# Sheet1.net
KiCad netlist of a schematic drawn in Altium Designer
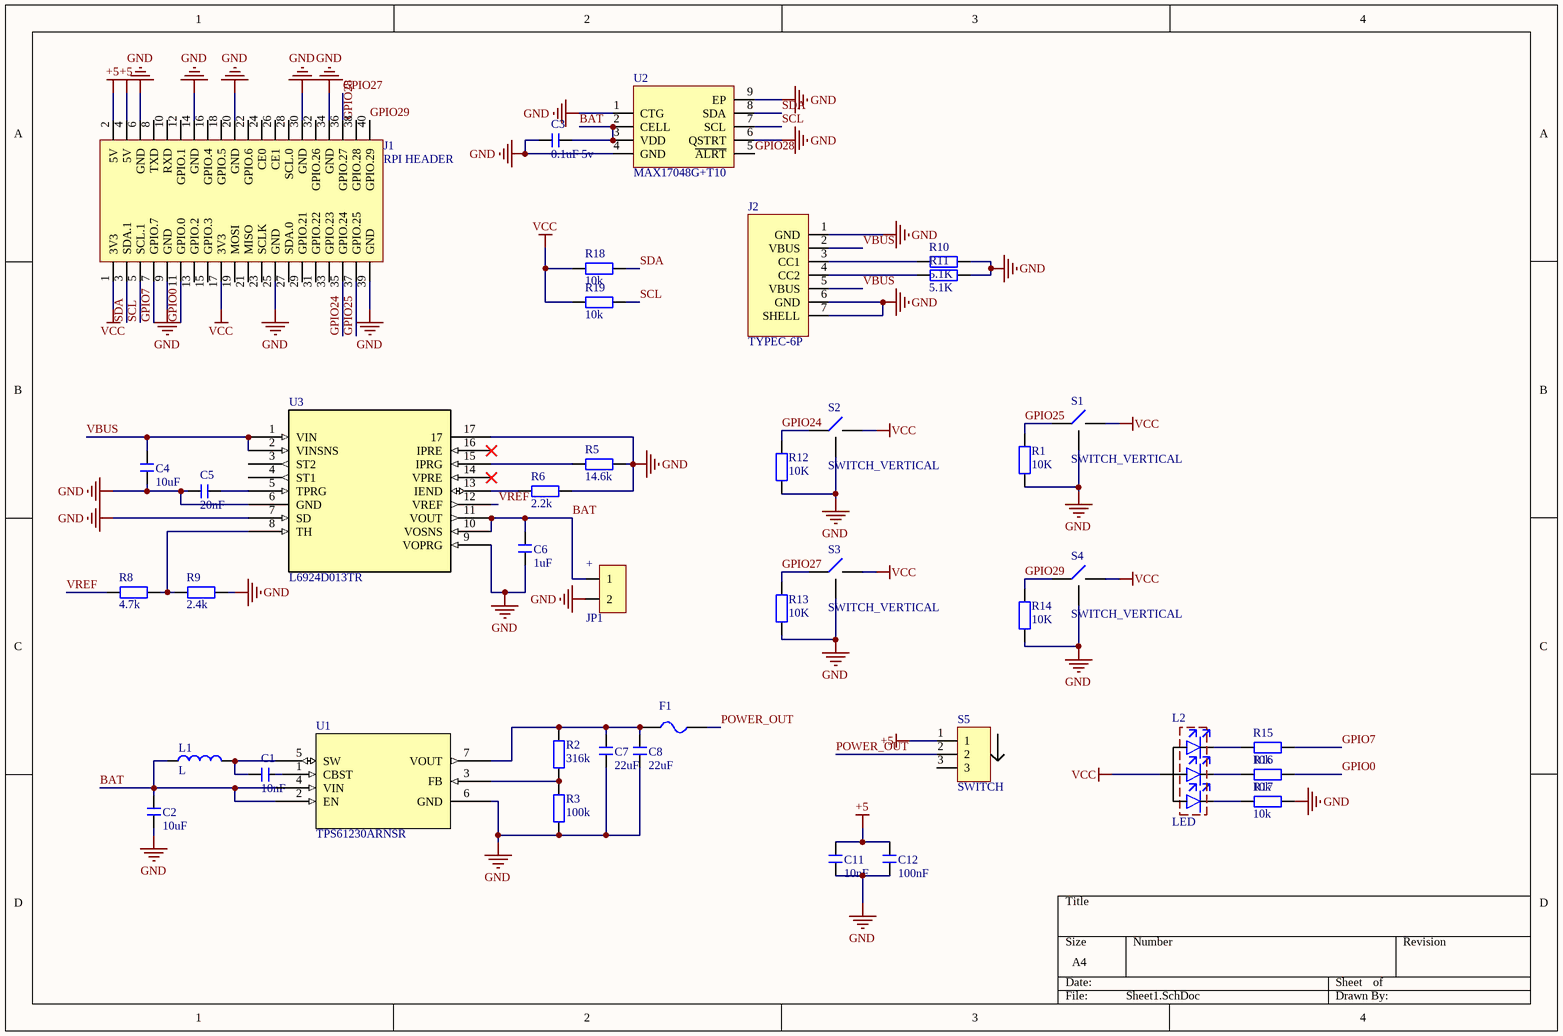
[diagram p0: Sheet1.SchDoc]

(export (version "E")
  (design (tool "Eeschema 10.0.6"))
  (components
    (comp (ref "C1")
      (value "10nF")
      (footprint "C 0603_M")
      (description "无极性贴片电容")
      (libsource (lib "元件库2") (part "C"))
    )
    (comp (ref "C2")
      (value "10uF")
      (footprint "C 0603_M")
      (description "无极性贴片电容")
      (libsource (lib "元件库2") (part "C"))
    )
    (comp (ref "C3")
      (value "0.1uF 5v")
      (footprint "C 0603_M")
      (description "无极性贴片电容")
      (libsource (lib "元件库2") (part "C"))
    )
    (comp (ref "C4")
      (value "10uF")
      (footprint "C 0603_M")
      (description "无极性贴片电容")
      (libsource (lib "元件库2") (part "C"))
    )
    (comp (ref "C5")
      (value "20nF")
      (footprint "C 0603_M")
      (description "无极性贴片电容")
      (libsource (lib "元件库2") (part "C"))
    )
    (comp (ref "C6")
      (value "1uF")
      (footprint "C 0603_M")
      (description "无极性贴片电容")
      (libsource (lib "元件库2") (part "C"))
    )
    (comp (ref "C7")
      (value "22uF")
      (footprint "C 0603_M")
      (description "无极性贴片电容")
      (libsource (lib "元件库2") (part "C"))
    )
    (comp (ref "C8")
      (value "22uF")
      (footprint "C 0603_M")
      (description "无极性贴片电容")
      (libsource (lib "元件库2") (part "C"))
    )
    (comp (ref "C11")
      (value "10nF")
      (footprint "C 0603_M")
      (description "无极性贴片电容")
      (libsource (lib "元件库2") (part "C"))
    )
    (comp (ref "C12")
      (value "100nF")
      (footprint "C 0603_M")
      (description "无极性贴片电容")
      (libsource (lib "元件库2") (part "C"))
    )
    (comp (ref "F1")
      (value "MSMD200-8V 2A")
      (footprint "FU 1206")
      (description "贴片保险丝")
      (fields (field (name "版权归属") "源创客"))
      (libsource (lib "Altium Designer 3D元件库") (part "FU"))
    )
    (comp (ref "J1")
      (value "RPI HEADER")
      (footprint "HEADER 2*20 BACK")
      (libsource (lib "Schlib1") (part "RPI HEADER"))
    )
    (comp (ref "J2")
      (value "TYPEC-6P")
      (footprint "TYPEC-6P-SMD")
      (libsource (lib "Schlib1") (part "TYPEC-6P"))
    )
    (comp (ref "JP1") (value "PH2.0 2P") (footprint "PH2.0 2P") (libsource (lib "Schlib1") (part "PH2.0 2P")))
    (comp (ref "L1") (value "L") (footprint "L SMD") (libsource (lib "Schlib1") (part "L")))
    (comp (ref "L2")
      (value "LED")
      (footprint "FM-3510RGBA-SG")
      (libsource (lib "Schlib1") (part "RGBLED_VERTICAL"))
    )
    (comp (ref "R1")
      (value "10K")
      (footprint "R 0603-HP")
      (description "贴片电阻")
      (fields (field (name "版权归属") "源创客"))
      (libsource (lib "Altium Designer 3D元件库") (part "R"))
    )
    (comp (ref "R2")
      (value "316k")
      (footprint "R 0603-HP")
      (description "贴片电阻")
      (fields (field (name "版权归属") "源创客"))
      (libsource (lib "Altium Designer 3D元件库") (part "R"))
    )
    (comp (ref "R3")
      (value "100k")
      (footprint "R 0603-HP")
      (description "贴片电阻")
      (fields (field (name "版权归属") "源创客"))
      (libsource (lib "Altium Designer 3D元件库") (part "R"))
    )
    (comp (ref "R5")
      (value "14.6k")
      (footprint "R 0603-HP")
      (description "贴片电阻")
      (fields (field (name "版权归属") "源创客"))
      (libsource (lib "Altium Designer 3D元件库") (part "R"))
    )
    (comp (ref "R6")
      (value "2.2k")
      (footprint "R 0603-HP")
      (description "贴片电阻")
      (fields (field (name "版权归属") "源创客"))
      (libsource (lib "Altium Designer 3D元件库") (part "R"))
    )
    (comp (ref "R8")
      (value "4.7k")
      (footprint "R 0603-HP")
      (description "贴片电阻")
      (fields (field (name "版权归属") "源创客"))
      (libsource (lib "Altium Designer 3D元件库") (part "R"))
    )
    (comp (ref "R9")
      (value "2.4k")
      (footprint "R 0603-HP")
      (description "贴片电阻")
      (fields (field (name "版权归属") "源创客"))
      (libsource (lib "Altium Designer 3D元件库") (part "R"))
    )
    (comp (ref "R10")
      (value "5.1K")
      (footprint "R 0603")
      (description "贴片电阻")
      (fields (field (name "版权归属") "源创客"))
      (libsource (lib "Altium Designer 3D元件库") (part "R"))
    )
    (comp (ref "R11")
      (value "5.1K")
      (footprint "R 0603")
      (description "贴片电阻")
      (fields (field (name "版权归属") "源创客"))
      (libsource (lib "Altium Designer 3D元件库") (part "R"))
    )
    (comp (ref "R12")
      (value "10K")
      (footprint "R 0603-HP")
      (description "贴片电阻")
      (fields (field (name "版权归属") "源创客"))
      (libsource (lib "Altium Designer 3D元件库") (part "R"))
    )
    (comp (ref "R13")
      (value "10K")
      (footprint "R 0603-HP")
      (description "贴片电阻")
      (fields (field (name "版权归属") "源创客"))
      (libsource (lib "Altium Designer 3D元件库") (part "R"))
    )
    (comp (ref "R14")
      (value "10K")
      (footprint "R 0603-HP")
      (description "贴片电阻")
      (fields (field (name "版权归属") "源创客"))
      (libsource (lib "Altium Designer 3D元件库") (part "R"))
    )
    (comp (ref "R15")
      (value "10k")
      (footprint "R 0603-HP")
      (description "贴片电阻")
      (fields (field (name "版权归属") "源创客"))
      (libsource (lib "Altium Designer 3D元件库") (part "R"))
    )
    (comp (ref "R16")
      (value "10k")
      (footprint "R 0603-HP")
      (description "贴片电阻")
      (fields (field (name "版权归属") "源创客"))
      (libsource (lib "Altium Designer 3D元件库") (part "R"))
    )
    (comp (ref "R17")
      (value "10k")
      (footprint "R 0603-HP")
      (description "贴片电阻")
      (fields (field (name "版权归属") "源创客"))
      (libsource (lib "Altium Designer 3D元件库") (part "R"))
    )
    (comp (ref "R18")
      (value "10k")
      (footprint "R 0603-HP")
      (description "贴片电阻")
      (fields (field (name "版权归属") "源创客"))
      (libsource (lib "Altium Designer 3D元件库") (part "R"))
    )
    (comp (ref "R19")
      (value "10k")
      (footprint "R 0603-HP")
      (description "贴片电阻")
      (fields (field (name "版权归属") "源创客"))
      (libsource (lib "Altium Designer 3D元件库") (part "R"))
    )
    (comp (ref "S1")
      (value "SWITCH_VERTICAL")
      (footprint "TA3-2W2-V-T/R")
      (libsource (lib "Schlib1") (part "SWITCH_VERTICAL"))
    )
    (comp (ref "S2")
      (value "SWITCH_VERTICAL")
      (footprint "TA3-2W2-V-T/R")
      (libsource (lib "Schlib1") (part "SWITCH_VERTICAL"))
    )
    (comp (ref "S3")
      (value "SWITCH_VERTICAL")
      (footprint "TA3-2W2-V-T/R")
      (libsource (lib "Schlib1") (part "SWITCH_VERTICAL"))
    )
    (comp (ref "S4")
      (value "SWITCH_VERTICAL")
      (footprint "TA3-2W2-V-T/R")
      (libsource (lib "Schlib1") (part "SWITCH_VERTICAL"))
    )
    (comp (ref "S5") (value "SWITCH") (footprint "SWITCH") (libsource (lib "Schlib1") (part "SWITCH")))
    (comp (ref "U1")
      (value "TPS61230ARNSR")
      (footprint "VQFN7_2X2_TEX-M")
      (description "No Description Available")
      (fields (field (name "COPYRIGHT") "Copyright (C) 2022 Ultra Librarian. All rights reserved."))
      (libsource (lib "Schlib1") (part "TPS61230ARNSR"))
    )
    (comp (ref "U2")
      (value "MAX17048G+T10")
      (footprint "TDFN-8_EP")
      (libsource (lib "Schlib1") (part "MAX17048G+T10"))
    )
    (comp (ref "U3")
      (value "L6924D013TR")
      (footprint "VFQFPN-16_STM-M")
      (description "No Description Available")
      (fields (field (name "COPYRIGHT") "Copyright (C) 2021 Accelerated Designs. All rights reserved"))
      (libsource (lib "Schlib1") (part "L6924D013TR"))
    )
  )
  (nets
    (net (code "1") (name "+5") (class "Default")
      (node (ref "C11") (pin "2") (pinfunction "2_2") (pintype "passive"))
      (node (ref "C12") (pin "2") (pinfunction "2_2") (pintype "passive"))
      (node (ref "J1") (pin "2") (pinfunction "5V_2") (pintype "passive"))
      (node (ref "J1") (pin "4") (pinfunction "5V_4") (pintype "passive"))
      (node (ref "S5") (pin "1") (pinfunction "1_1") (pintype "passive"))
    )
    (net (code "2") (name "/BAT") (class "Default")
      (node (ref "C2") (pin "1") (pinfunction "1_1") (pintype "passive"))
      (node (ref "C3") (pin "2") (pinfunction "2_2") (pintype "passive"))
      (node (ref "C6") (pin "2") (pinfunction "2_2") (pintype "passive"))
      (node (ref "JP1") (pin "1") (pinfunction "1_1") (pintype "passive"))
      (node (ref "L1") (pin "1") (pinfunction "1_1") (pintype "passive"))
      (node (ref "U1") (pin "2") (pinfunction "EN_2") (pintype "input"))
      (node (ref "U1") (pin "4") (pinfunction "VIN_4") (pintype "input"))
      (node (ref "U2") (pin "2") (pinfunction "CELL_2") (pintype "passive"))
      (node (ref "U2") (pin "3") (pinfunction "VDD_3") (pintype "passive"))
      (node (ref "U3") (pin "10") (pinfunction "VOSNS_10") (pintype "input"))
      (node (ref "U3") (pin "11") (pinfunction "VOUT_11") (pintype "output"))
    )
    (net (code "3") (name "/GPIO0") (class "Default")
      (node (ref "J1") (pin "11") (pinfunction "GPIO.0_11") (pintype "passive"))
      (node (ref "R16") (pin "1") (pinfunction "1_1") (pintype "passive"))
    )
    (net (code "4") (name "/GPIO7") (class "Default")
      (node (ref "J1") (pin "7") (pinfunction "GPIO.7_7") (pintype "passive"))
      (node (ref "R15") (pin "1") (pinfunction "1_1") (pintype "passive"))
    )
    (net (code "5") (name "/GPIO24") (class "Default")
      (node (ref "J1") (pin "35") (pinfunction "GPIO.24_35") (pintype "passive"))
      (node (ref "R12") (pin "1") (pinfunction "1_1") (pintype "passive"))
      (node (ref "S2") (pin "1") (pinfunction "1_1") (pintype "passive"))
    )
    (net (code "6") (name "/GPIO25") (class "Default")
      (node (ref "J1") (pin "37") (pinfunction "GPIO.25_37") (pintype "passive"))
      (node (ref "R1") (pin "1") (pinfunction "1_1") (pintype "passive"))
      (node (ref "S1") (pin "1") (pinfunction "1_1") (pintype "passive"))
    )
    (net (code "7") (name "/GPIO27") (class "Default")
      (node (ref "J1") (pin "36") (pinfunction "GPIO.27_36") (pintype "passive"))
      (node (ref "R13") (pin "1") (pinfunction "1_1") (pintype "passive"))
      (node (ref "S3") (pin "1") (pinfunction "1_1") (pintype "passive"))
    )
    (net (code "8") (name "/GPIO28") (class "Default")
      (node (ref "J1") (pin "38") (pinfunction "GPIO.28_38") (pintype "passive"))
      (node (ref "U2") (pin "5") (pinfunction "~{ALRT}_5") (pintype "passive"))
    )
    (net (code "9") (name "/GPIO29") (class "Default")
      (node (ref "J1") (pin "40") (pinfunction "GPIO.29_40") (pintype "passive"))
      (node (ref "R14") (pin "1") (pinfunction "1_1") (pintype "passive"))
      (node (ref "S4") (pin "1") (pinfunction "1_1") (pintype "passive"))
    )
    (net (code "10") (name "/POWER_OUT") (class "Default")
      (node (ref "F1") (pin "2") (pinfunction "2_2") (pintype "passive"))
      (node (ref "S5") (pin "2") (pinfunction "2_2") (pintype "passive"))
    )
    (net (code "11") (name "/SCL") (class "Default")
      (node (ref "J1") (pin "5") (pinfunction "SCL.1_5") (pintype "passive"))
      (node (ref "R19") (pin "2") (pinfunction "2_2") (pintype "passive"))
      (node (ref "U2") (pin "7") (pinfunction "SCL_7") (pintype "passive"))
    )
    (net (code "12") (name "/SDA") (class "Default")
      (node (ref "J1") (pin "3") (pinfunction "SDA.1_3") (pintype "passive"))
      (node (ref "R18") (pin "2") (pinfunction "2_2") (pintype "passive"))
      (node (ref "U2") (pin "8") (pinfunction "SDA_8") (pintype "passive"))
    )
    (net (code "13") (name "/VBUS") (class "Default")
      (node (ref "C4") (pin "2") (pinfunction "2_2") (pintype "passive"))
      (node (ref "J2") (pin "2") (pinfunction "VBUS_2") (pintype "passive"))
      (node (ref "J2") (pin "5") (pinfunction "VBUS_5") (pintype "passive"))
      (node (ref "U3") (pin "1") (pinfunction "VIN_1") (pintype "input"))
      (node (ref "U3") (pin "2") (pinfunction "VINSNS_2") (pintype "input"))
    )
    (net (code "14") (name "/VREF") (class "Default")
      (node (ref "R8") (pin "2") (pinfunction "2_2") (pintype "passive"))
      (node (ref "U3") (pin "12") (pinfunction "VREF_12") (pintype "output"))
    )
    (net (code "15") (name "GND") (class "Default")
      (node (ref "C11") (pin "1") (pinfunction "1_1") (pintype "passive"))
      (node (ref "C12") (pin "1") (pinfunction "1_1") (pintype "passive"))
      (node (ref "C2") (pin "2") (pinfunction "2_2") (pintype "passive"))
      (node (ref "C3") (pin "1") (pinfunction "1_1") (pintype "passive"))
      (node (ref "C4") (pin "1") (pinfunction "1_1") (pintype "passive"))
      (node (ref "C5") (pin "1") (pinfunction "1_1") (pintype "passive"))
      (node (ref "C6") (pin "1") (pinfunction "1_1") (pintype "passive"))
      (node (ref "C7") (pin "1") (pinfunction "1_1") (pintype "passive"))
      (node (ref "C8") (pin "1") (pinfunction "1_1") (pintype "passive"))
      (node (ref "J1") (pin "14") (pinfunction "GND_14") (pintype "passive"))
      (node (ref "J1") (pin "20") (pinfunction "GND_20") (pintype "passive"))
      (node (ref "J1") (pin "25") (pinfunction "GND_25") (pintype "passive"))
      (node (ref "J1") (pin "30") (pinfunction "GND_30") (pintype "passive"))
      (node (ref "J1") (pin "34") (pinfunction "GND_34") (pintype "passive"))
      (node (ref "J1") (pin "39") (pinfunction "GND_39") (pintype "passive"))
      (node (ref "J1") (pin "6") (pinfunction "GND_6") (pintype "passive"))
      (node (ref "J1") (pin "9") (pinfunction "GND_9") (pintype "passive"))
      (node (ref "J2") (pin "1") (pinfunction "GND_1") (pintype "passive"))
      (node (ref "J2") (pin "6") (pinfunction "GND_6") (pintype "passive"))
      (node (ref "J2") (pin "7") (pinfunction "SHELL_7") (pintype "passive"))
      (node (ref "JP1") (pin "2") (pinfunction "2_2") (pintype "passive"))
      (node (ref "R1") (pin "2") (pinfunction "2_2") (pintype "passive"))
      (node (ref "R10") (pin "2") (pinfunction "2_2") (pintype "passive"))
      (node (ref "R11") (pin "2") (pinfunction "2_2") (pintype "passive"))
      (node (ref "R12") (pin "2") (pinfunction "2_2") (pintype "passive"))
      (node (ref "R13") (pin "2") (pinfunction "2_2") (pintype "passive"))
      (node (ref "R14") (pin "2") (pinfunction "2_2") (pintype "passive"))
      (node (ref "R17") (pin "1") (pinfunction "1_1") (pintype "passive"))
      (node (ref "R3") (pin "2") (pinfunction "2_2") (pintype "passive"))
      (node (ref "R5") (pin "1") (pinfunction "1_1") (pintype "passive"))
      (node (ref "R6") (pin "1") (pinfunction "1_1") (pintype "passive"))
      (node (ref "R9") (pin "1") (pinfunction "1_1") (pintype "passive"))
      (node (ref "S1") (pin "3") (pinfunction "3_3") (pintype "passive"))
      (node (ref "S2") (pin "3") (pinfunction "3_3") (pintype "passive"))
      (node (ref "S3") (pin "3") (pinfunction "3_3") (pintype "passive"))
      (node (ref "S4") (pin "3") (pinfunction "3_3") (pintype "passive"))
      (node (ref "U1") (pin "6") (pinfunction "GND_6") (pintype "power_in"))
      (node (ref "U2") (pin "1") (pinfunction "CTG_1") (pintype "passive"))
      (node (ref "U2") (pin "4") (pinfunction "GND_4") (pintype "passive"))
      (node (ref "U2") (pin "6") (pinfunction "QSTRT_6") (pintype "passive"))
      (node (ref "U2") (pin "9") (pinfunction "EP_9") (pintype "passive"))
      (node (ref "U3") (pin "17") (pinfunction "17_17") (pintype "passive"))
      (node (ref "U3") (pin "6") (pinfunction "GND_6") (pintype "passive"))
      (node (ref "U3") (pin "7") (pinfunction "SD_7") (pintype "input"))
      (node (ref "U3") (pin "9") (pinfunction "VOPRG_9") (pintype "input"))
    )
    (net (code "16") (name "Net-(J2-CC1)") (class "Default")
      (node (ref "J2") (pin "3") (pinfunction "CC1_3") (pintype "passive"))
      (node (ref "R10") (pin "1") (pinfunction "1_1") (pintype "passive"))
    )
    (net (code "17") (name "Net-(J2-CC2)") (class "Default")
      (node (ref "J2") (pin "4") (pinfunction "CC2_4") (pintype "passive"))
      (node (ref "R11") (pin "1") (pinfunction "1_1") (pintype "passive"))
    )
    (net (code "18") (name "Net-(L2-B)") (class "Default")
      (node (ref "L2") (pin "1") (pinfunction "B_1") (pintype "passive"))
      (node (ref "R17") (pin "2") (pinfunction "2_2") (pintype "passive"))
    )
    (net (code "19") (name "Net-(L2-G)") (class "Default")
      (node (ref "L2") (pin "3") (pinfunction "G_3") (pintype "passive"))
      (node (ref "R16") (pin "2") (pinfunction "2_2") (pintype "passive"))
    )
    (net (code "20") (name "Net-(L2-R)") (class "Default")
      (node (ref "L2") (pin "4") (pinfunction "R_4") (pintype "passive"))
      (node (ref "R15") (pin "2") (pinfunction "2_2") (pintype "passive"))
    )
    (net (code "21") (name "Net-(U1-CBST)") (class "Default")
      (node (ref "C1") (pin "1") (pinfunction "1_1") (pintype "passive"))
      (node (ref "U1") (pin "1") (pinfunction "CBST_1") (pintype "input"))
    )
    (net (code "22") (name "Net-(U1-FB)") (class "Default")
      (node (ref "R2") (pin "1") (pinfunction "1_1") (pintype "passive"))
      (node (ref "R3") (pin "1") (pinfunction "1_1") (pintype "passive"))
      (node (ref "U1") (pin "3") (pinfunction "FB_3") (pintype "input"))
    )
    (net (code "23") (name "Net-(U1-SW)") (class "Default")
      (node (ref "C1") (pin "2") (pinfunction "2_2") (pintype "passive"))
      (node (ref "L1") (pin "2") (pinfunction "2_2") (pintype "passive"))
      (node (ref "U1") (pin "5") (pinfunction "SW_5") (pintype "bidirectional"))
    )
    (net (code "24") (name "Net-(U1-VOUT)") (class "Default")
      (node (ref "C7") (pin "2") (pinfunction "2_2") (pintype "passive"))
      (node (ref "C8") (pin "2") (pinfunction "2_2") (pintype "passive"))
      (node (ref "F1") (pin "1") (pinfunction "1_1") (pintype "passive"))
      (node (ref "R2") (pin "2") (pinfunction "2_2") (pintype "passive"))
      (node (ref "U1") (pin "7") (pinfunction "VOUT_7") (pintype "output"))
    )
    (net (code "25") (name "Net-(U3-IEND)") (class "Default")
      (node (ref "R6") (pin "2") (pinfunction "2_2") (pintype "passive"))
      (node (ref "U3") (pin "13") (pinfunction "IEND_13") (pintype "bidirectional"))
    )
    (net (code "26") (name "Net-(U3-IPRG)") (class "Default")
      (node (ref "R5") (pin "2") (pinfunction "2_2") (pintype "passive"))
      (node (ref "U3") (pin "15") (pinfunction "IPRG_15") (pintype "input"))
    )
    (net (code "27") (name "Net-(U3-TH)") (class "Default")
      (node (ref "R8") (pin "1") (pinfunction "1_1") (pintype "passive"))
      (node (ref "R9") (pin "2") (pinfunction "2_2") (pintype "passive"))
      (node (ref "U3") (pin "8") (pinfunction "TH_8") (pintype "input"))
    )
    (net (code "28") (name "Net-(U3-TPRG)") (class "Default")
      (node (ref "C5") (pin "2") (pinfunction "2_2") (pintype "passive"))
      (node (ref "U3") (pin "5") (pinfunction "TPRG_5") (pintype "input"))
    )
    (net (code "29") (name "VCC") (class "Default")
      (node (ref "J1") (pin "1") (pinfunction "3V3_1") (pintype "power_in"))
      (node (ref "J1") (pin "17") (pinfunction "3V3_17") (pintype "passive"))
      (node (ref "L2") (pin "2") (pinfunction "V_2") (pintype "passive"))
      (node (ref "R18") (pin "1") (pinfunction "1_1") (pintype "passive"))
      (node (ref "R19") (pin "1") (pinfunction "1_1") (pintype "passive"))
      (node (ref "S1") (pin "2") (pinfunction "2_2") (pintype "passive"))
      (node (ref "S2") (pin "2") (pinfunction "2_2") (pintype "passive"))
      (node (ref "S3") (pin "2") (pinfunction "2_2") (pintype "passive"))
      (node (ref "S4") (pin "2") (pinfunction "2_2") (pintype "passive"))
    )
    (net (code "30") (name "unconnected-(J1-CE0-Pad24)") (class "Default")
      (node (ref "J1") (pin "24") (pinfunction "CE0_24") (pintype "passive"))
    )
    (net (code "31") (name "unconnected-(J1-CE1-Pad26)") (class "Default")
      (node (ref "J1") (pin "26") (pinfunction "CE1_26") (pintype "passive"))
    )
    (net (code "32") (name "unconnected-(J1-GPIO.1-Pad12)") (class "Default")
      (node (ref "J1") (pin "12") (pinfunction "GPIO.1_12") (pintype "passive"))
    )
    (net (code "33") (name "unconnected-(J1-GPIO.2-Pad13)") (class "Default")
      (node (ref "J1") (pin "13") (pinfunction "GPIO.2_13") (pintype "passive"))
    )
    (net (code "34") (name "unconnected-(J1-GPIO.3-Pad15)") (class "Default")
      (node (ref "J1") (pin "15") (pinfunction "GPIO.3_15") (pintype "passive"))
    )
    (net (code "35") (name "unconnected-(J1-GPIO.4-Pad16)") (class "Default")
      (node (ref "J1") (pin "16") (pinfunction "GPIO.4_16") (pintype "passive"))
    )
    (net (code "36") (name "unconnected-(J1-GPIO.5-Pad18)") (class "Default")
      (node (ref "J1") (pin "18") (pinfunction "GPIO.5_18") (pintype "passive"))
    )
    (net (code "37") (name "unconnected-(J1-GPIO.6-Pad22)") (class "Default")
      (node (ref "J1") (pin "22") (pinfunction "GPIO.6_22") (pintype "passive"))
    )
    (net (code "38") (name "unconnected-(J1-GPIO.21-Pad29)") (class "Default")
      (node (ref "J1") (pin "29") (pinfunction "GPIO.21_29") (pintype "passive"))
    )
    (net (code "39") (name "unconnected-(J1-GPIO.22-Pad31)") (class "Default")
      (node (ref "J1") (pin "31") (pinfunction "GPIO.22_31") (pintype "passive"))
    )
    (net (code "40") (name "unconnected-(J1-GPIO.23-Pad33)") (class "Default")
      (node (ref "J1") (pin "33") (pinfunction "GPIO.23_33") (pintype "passive"))
    )
    (net (code "41") (name "unconnected-(J1-GPIO.26-Pad32)") (class "Default")
      (node (ref "J1") (pin "32") (pinfunction "GPIO.26_32") (pintype "passive"))
    )
    (net (code "42") (name "unconnected-(J1-MISO-Pad21)") (class "Default")
      (node (ref "J1") (pin "21") (pinfunction "MISO_21") (pintype "passive"))
    )
    (net (code "43") (name "unconnected-(J1-MOSI-Pad19)") (class "Default")
      (node (ref "J1") (pin "19") (pinfunction "MOSI_19") (pintype "passive"))
    )
    (net (code "44") (name "unconnected-(J1-RXD-Pad10)") (class "Default")
      (node (ref "J1") (pin "10") (pinfunction "RXD_10") (pintype "passive"))
    )
    (net (code "45") (name "unconnected-(J1-SCL.0-Pad28)") (class "Default")
      (node (ref "J1") (pin "28") (pinfunction "SCL.0_28") (pintype "passive"))
    )
    (net (code "46") (name "unconnected-(J1-SCLK-Pad23)") (class "Default")
      (node (ref "J1") (pin "23") (pinfunction "SCLK_23") (pintype "passive"))
    )
    (net (code "47") (name "unconnected-(J1-SDA.0-Pad27)") (class "Default")
      (node (ref "J1") (pin "27") (pinfunction "SDA.0_27") (pintype "passive"))
    )
    (net (code "48") (name "unconnected-(J1-TXD-Pad8)") (class "Default")
      (node (ref "J1") (pin "8") (pinfunction "TXD_8") (pintype "passive"))
    )
    (net (code "49") (name "unconnected-(S5-Pad3)") (class "Default")
      (node (ref "S5") (pin "3") (pinfunction "3_3") (pintype "passive"))
    )
    (net (code "50") (name "unconnected-(U3-IPRE-Pad16)") (class "Default")
      (node (ref "U3") (pin "16") (pinfunction "IPRE_16") (pintype "input+no_connect"))
    )
    (net (code "51") (name "unconnected-(U3-ST1-Pad4)") (class "Default")
      (node (ref "U3") (pin "4") (pinfunction "ST1_4") (pintype "output"))
    )
    (net (code "52") (name "unconnected-(U3-ST2-Pad3)") (class "Default")
      (node (ref "U3") (pin "3") (pinfunction "ST2_3") (pintype "output"))
    )
    (net (code "53") (name "unconnected-(U3-VPRE-Pad14)") (class "Default")
      (node (ref "U3") (pin "14") (pinfunction "VPRE_14") (pintype "input+no_connect"))
    )
  )
)
